# MURUNGI_ANGELLA_-MERICI_SOFT_LIGHTS.net
KiCad netlist of a schematic drawn in EasyEDA
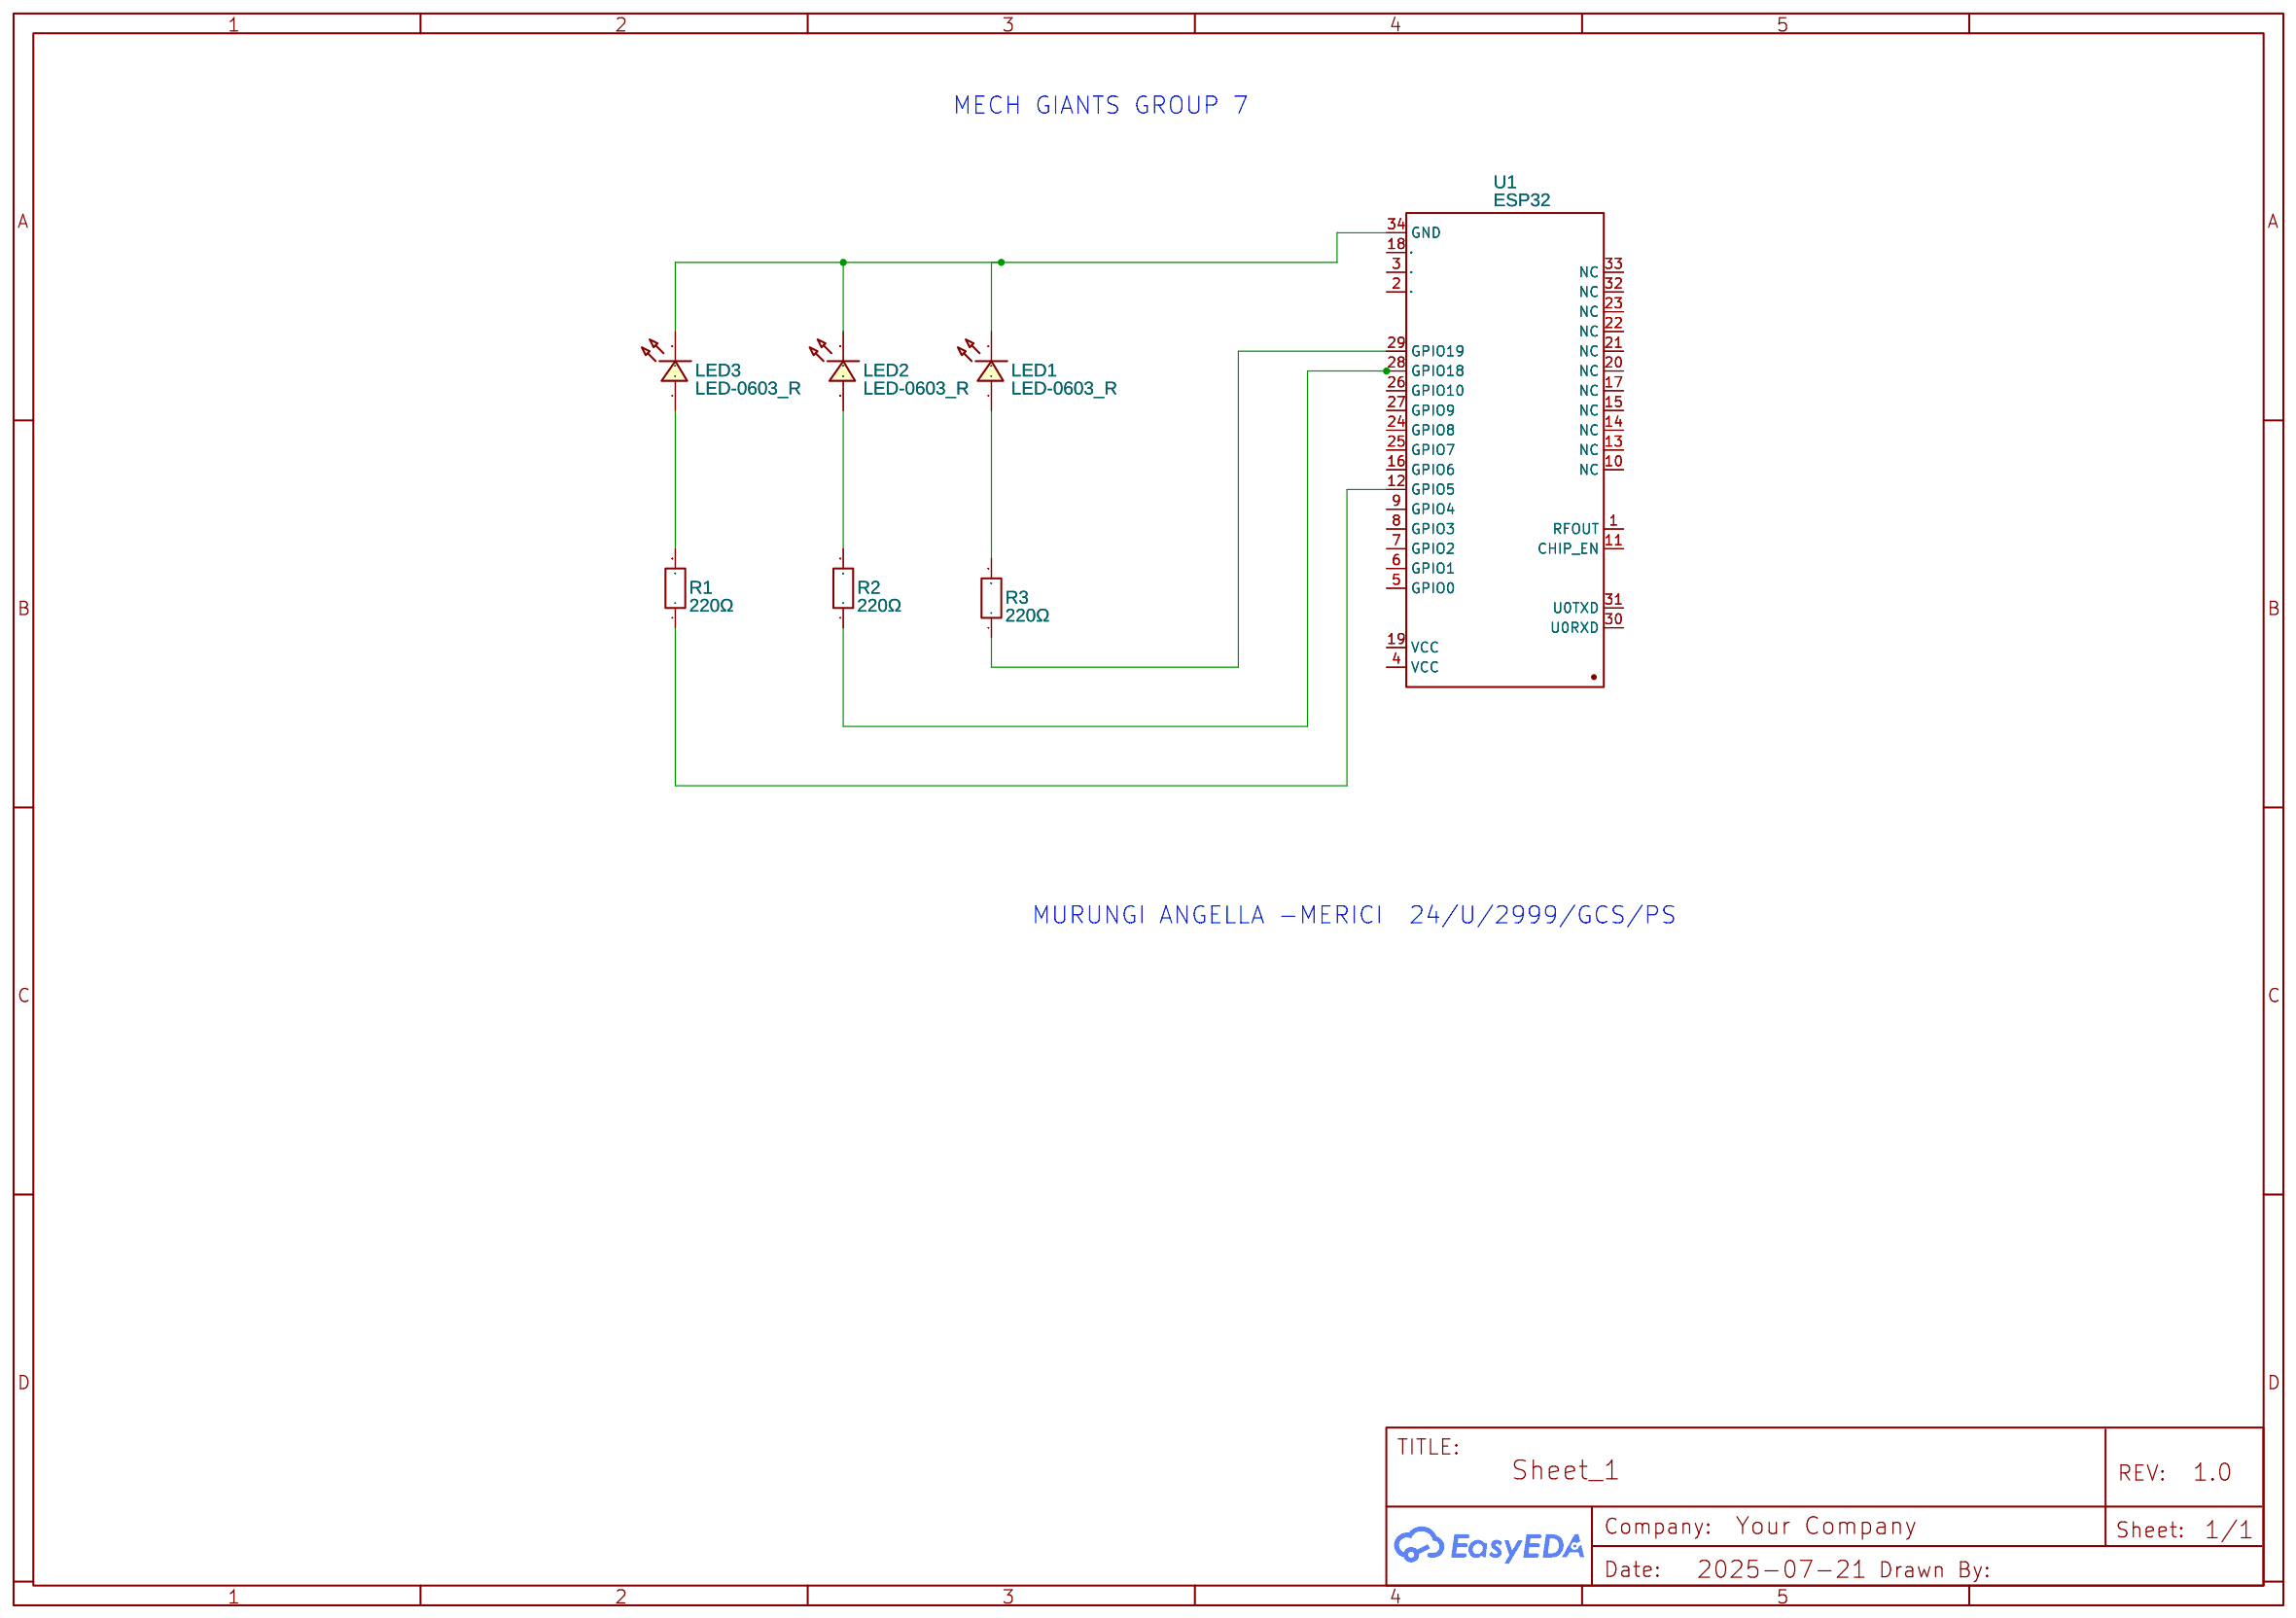
[diagram p0: schematic sheet]

(export (version "E")
  (design (tool "Eeschema 10.0.6"))
  (components
    (comp (ref "LED1")
      (value "LED-0603_R")
      (fields
        (field (name "Manufacturer Part") "19-217/R6C-AL1M2VY/3T")
        (field (name "Manufacturer") "EVERLIGHT(台湾亿光)")
      )
      (libsource (lib "") (part "LED-0603_R"))
    )
    (comp (ref "LED2")
      (value "LED-0603_R")
      (fields
        (field (name "Manufacturer Part") "19-217/R6C-AL1M2VY/3T")
        (field (name "Manufacturer") "EVERLIGHT(台湾亿光)")
      )
      (libsource (lib "") (part "LED-0603_R"))
    )
    (comp (ref "LED3")
      (value "LED-0603_R")
      (fields
        (field (name "Manufacturer Part") "19-217/R6C-AL1M2VY/3T")
        (field (name "Manufacturer") "EVERLIGHT(台湾亿光)")
      )
      (libsource (lib "") (part "LED-0603_R"))
    )
    (comp (ref "R1")
      (value "220Ω")
      (fields
        (field (name "Manufacturer Part") "MM204VF220RTKRTR3K0")
        (field (name "Manufacturer") "Firstohm(第一电阻)")
      )
      (libsource (lib "") (part "MM204VF220RTKRTR3K0"))
    )
    (comp (ref "R2")
      (value "220Ω")
      (fields
        (field (name "Manufacturer Part") "MM204VF220RTKRTR3K0")
        (field (name "Manufacturer") "Firstohm(第一电阻)")
      )
      (libsource (lib "") (part "MM204VF220RTKRTR3K0"))
    )
    (comp (ref "R3")
      (value "220Ω")
      (fields
        (field (name "Manufacturer Part") "MM204VF220RTKRTR3K0")
        (field (name "Manufacturer") "Firstohm(第一电阻)")
      )
      (libsource (lib "") (part "MM204VF220RTKRTR3K0"))
    )
    (comp (ref "U1")
      (value "ESP32")
      (fields (field (name "Manufacturer Part") "RF-WM-ESP32B1") (field (name "Manufacturer") "RF-star(信驰达)"))
      (libsource (lib "") (part "RF-WM-ESP32B1"))
    )
  )
  (nets
    (net (code "1") (name "Net-(LED1-Pad1)") (class "Default")
      (node (ref "LED1") (pin "1") (pinfunction "1_1") (pintype "unspecified"))
      (node (ref "R3") (pin "2") (pinfunction "2_2") (pintype "unspecified"))
    )
    (net (code "2") (name "Net-(LED1-Pad2)") (class "Default")
      (node (ref "LED1") (pin "2") (pinfunction "2_2") (pintype "unspecified"))
      (node (ref "LED2") (pin "2") (pinfunction "2_2") (pintype "unspecified"))
      (node (ref "LED3") (pin "2") (pinfunction "2_2") (pintype "unspecified"))
      (node (ref "U1") (pin "34") (pinfunction "GND_34") (pintype "unspecified"))
    )
    (net (code "3") (name "Net-(LED2-Pad1)") (class "Default")
      (node (ref "LED2") (pin "1") (pinfunction "1_1") (pintype "unspecified"))
      (node (ref "R2") (pin "2") (pinfunction "2_2") (pintype "unspecified"))
    )
    (net (code "4") (name "Net-(LED3-Pad1)") (class "Default")
      (node (ref "LED3") (pin "1") (pinfunction "1_1") (pintype "unspecified"))
      (node (ref "R1") (pin "2") (pinfunction "2_2") (pintype "unspecified"))
    )
    (net (code "5") (name "Net-(U1-GPIO5)") (class "Default")
      (node (ref "R1") (pin "1") (pinfunction "1_1") (pintype "unspecified"))
      (node (ref "U1") (pin "12") (pinfunction "GPIO5_12") (pintype "unspecified"))
    )
    (net (code "6") (name "Net-(U1-GPIO18)") (class "Default")
      (node (ref "R2") (pin "1") (pinfunction "1_1") (pintype "unspecified"))
      (node (ref "U1") (pin "28") (pinfunction "GPIO18_28") (pintype "unspecified"))
    )
    (net (code "7") (name "Net-(U1-GPIO19)") (class "Default")
      (node (ref "R3") (pin "1") (pinfunction "1_1") (pintype "unspecified"))
      (node (ref "U1") (pin "29") (pinfunction "GPIO19_29") (pintype "unspecified"))
    )
    (net (code "8") (name "unconnected-(U1-CHIP_EN-Pad11)") (class "Default")
      (node (ref "U1") (pin "11") (pinfunction "CHIP_EN_11") (pintype "unspecified"))
    )
    (net (code "9") (name "unconnected-(U1-GND-Pad2)") (class "Default")
      (node (ref "U1") (pin "2") (pinfunction "GND_2") (pintype "unspecified"))
    )
    (net (code "10") (name "unconnected-(U1-GND-Pad3)") (class "Default")
      (node (ref "U1") (pin "3") (pinfunction "GND_3") (pintype "unspecified"))
    )
    (net (code "11") (name "unconnected-(U1-GND-Pad18)") (class "Default")
      (node (ref "U1") (pin "18") (pinfunction "GND_18") (pintype "unspecified"))
    )
    (net (code "12") (name "unconnected-(U1-GPIO0-Pad5)") (class "Default")
      (node (ref "U1") (pin "5") (pinfunction "GPIO0_5") (pintype "unspecified"))
    )
    (net (code "13") (name "unconnected-(U1-GPIO1-Pad6)") (class "Default")
      (node (ref "U1") (pin "6") (pinfunction "GPIO1_6") (pintype "unspecified"))
    )
    (net (code "14") (name "unconnected-(U1-GPIO2-Pad7)") (class "Default")
      (node (ref "U1") (pin "7") (pinfunction "GPIO2_7") (pintype "unspecified"))
    )
    (net (code "15") (name "unconnected-(U1-GPIO3-Pad8)") (class "Default")
      (node (ref "U1") (pin "8") (pinfunction "GPIO3_8") (pintype "unspecified"))
    )
    (net (code "16") (name "unconnected-(U1-GPIO4-Pad9)") (class "Default")
      (node (ref "U1") (pin "9") (pinfunction "GPIO4_9") (pintype "unspecified"))
    )
    (net (code "17") (name "unconnected-(U1-GPIO6-Pad16)") (class "Default")
      (node (ref "U1") (pin "16") (pinfunction "GPIO6_16") (pintype "unspecified"))
    )
    (net (code "18") (name "unconnected-(U1-GPIO7-Pad25)") (class "Default")
      (node (ref "U1") (pin "25") (pinfunction "GPIO7_25") (pintype "unspecified"))
    )
    (net (code "19") (name "unconnected-(U1-GPIO8-Pad24)") (class "Default")
      (node (ref "U1") (pin "24") (pinfunction "GPIO8_24") (pintype "unspecified"))
    )
    (net (code "20") (name "unconnected-(U1-GPIO9-Pad27)") (class "Default")
      (node (ref "U1") (pin "27") (pinfunction "GPIO9_27") (pintype "unspecified"))
    )
    (net (code "21") (name "unconnected-(U1-GPIO10-Pad26)") (class "Default")
      (node (ref "U1") (pin "26") (pinfunction "GPIO10_26") (pintype "unspecified"))
    )
    (net (code "22") (name "unconnected-(U1-NC-Pad10)") (class "Default")
      (node (ref "U1") (pin "10") (pinfunction "NC_10") (pintype "unspecified"))
    )
    (net (code "23") (name "unconnected-(U1-NC-Pad13)") (class "Default")
      (node (ref "U1") (pin "13") (pinfunction "NC_13") (pintype "unspecified"))
    )
    (net (code "24") (name "unconnected-(U1-NC-Pad14)") (class "Default")
      (node (ref "U1") (pin "14") (pinfunction "NC_14") (pintype "unspecified"))
    )
    (net (code "25") (name "unconnected-(U1-NC-Pad15)") (class "Default")
      (node (ref "U1") (pin "15") (pinfunction "NC_15") (pintype "unspecified"))
    )
    (net (code "26") (name "unconnected-(U1-NC-Pad17)") (class "Default")
      (node (ref "U1") (pin "17") (pinfunction "NC_17") (pintype "unspecified"))
    )
    (net (code "27") (name "unconnected-(U1-NC-Pad20)") (class "Default")
      (node (ref "U1") (pin "20") (pinfunction "NC_20") (pintype "unspecified"))
    )
    (net (code "28") (name "unconnected-(U1-NC-Pad21)") (class "Default")
      (node (ref "U1") (pin "21") (pinfunction "NC_21") (pintype "unspecified"))
    )
    (net (code "29") (name "unconnected-(U1-NC-Pad22)") (class "Default")
      (node (ref "U1") (pin "22") (pinfunction "NC_22") (pintype "unspecified"))
    )
    (net (code "30") (name "unconnected-(U1-NC-Pad23)") (class "Default")
      (node (ref "U1") (pin "23") (pinfunction "NC_23") (pintype "unspecified"))
    )
    (net (code "31") (name "unconnected-(U1-NC-Pad32)") (class "Default")
      (node (ref "U1") (pin "32") (pinfunction "NC_32") (pintype "unspecified"))
    )
    (net (code "32") (name "unconnected-(U1-NC-Pad33)") (class "Default")
      (node (ref "U1") (pin "33") (pinfunction "NC_33") (pintype "unspecified"))
    )
    (net (code "33") (name "unconnected-(U1-RFOUT-Pad1)") (class "Default")
      (node (ref "U1") (pin "1") (pinfunction "RFOUT_1") (pintype "unspecified"))
    )
    (net (code "34") (name "unconnected-(U1-U0RXD-Pad30)") (class "Default")
      (node (ref "U1") (pin "30") (pinfunction "U0RXD_30") (pintype "unspecified"))
    )
    (net (code "35") (name "unconnected-(U1-U0TXD-Pad31)") (class "Default")
      (node (ref "U1") (pin "31") (pinfunction "U0TXD_31") (pintype "unspecified"))
    )
    (net (code "36") (name "unconnected-(U1-VCC-Pad4)") (class "Default")
      (node (ref "U1") (pin "4") (pinfunction "VCC_4") (pintype "unspecified"))
    )
    (net (code "37") (name "unconnected-(U1-VCC-Pad19)") (class "Default")
      (node (ref "U1") (pin "19") (pinfunction "VCC_19") (pintype "unspecified"))
    )
  )
)
